# amc7135-by-16-19mm-led-aux-driver-mk-1_0.net
KiCad netlist of a schematic drawn in EAGLE
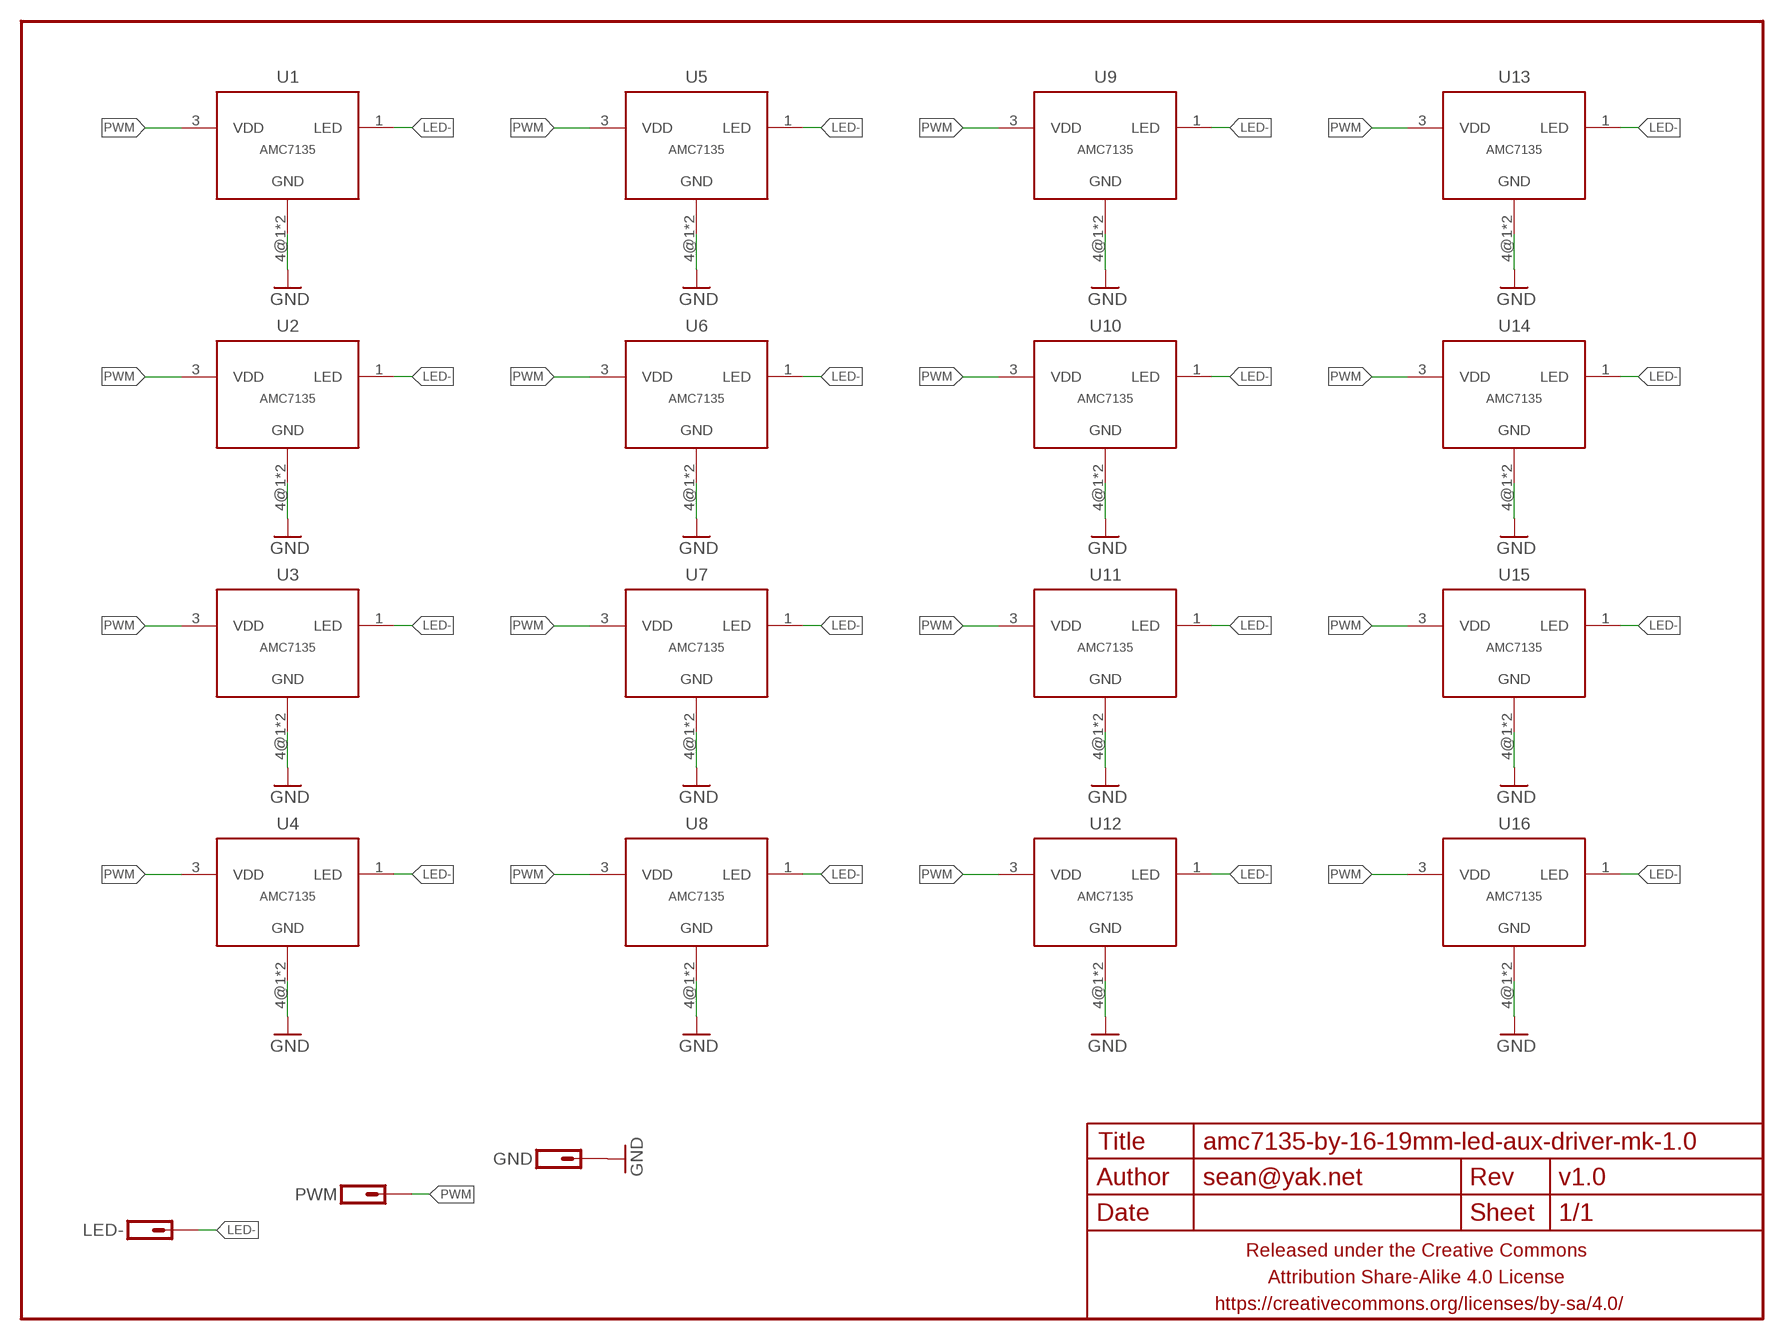
[diagram p0: schematic, sheet 1]

(export (version "E")
  (design (tool "Eeschema 10.0.6"))
  (components
    (comp (ref "FRAME1")
      (value "FRAME-LETTERNO_PACKAGE")
      (footprint "eagle-import:DUMMY")
      (fields (field (name "DESIGNER") "sean@yak.net") (field (name "VERSION") "v1.0"))
      (libsource (lib "eagle-import") (part "FRAME-LETTERNO_PACKAGE"))
    )
    (comp (ref "GND")
      (value "M01PTH-1.2MM-NS")
      (footprint "eagle-import:1X01-1.2MM-NS")
      (libsource (lib "eagle-import") (part "M01PTH-1.2MM-NS"))
    )
    (comp (ref "LED-")
      (value "M01PTH-1.2MM-NS")
      (footprint "eagle-import:1X01-1.2MM-NS")
      (libsource (lib "eagle-import") (part "M01PTH-1.2MM-NS"))
    )
    (comp (ref "PWM")
      (value "M01PTH-0.9MM-CIR")
      (footprint "eagle-import:1X01-0.9MM-CIR")
      (libsource (lib "eagle-import") (part "M01PTH-0.9MM-CIR"))
    )
    (comp (ref "U1")
      (value "AMC7135")
      (footprint "eagle-import:SOT89-ROUNDED-SMALLER")
      (libsource (lib "eagle-import") (part "AMC7135ROUNDEDSMALER"))
    )
    (comp (ref "U2")
      (value "AMC7135")
      (footprint "eagle-import:SOT89-ROUNDED-SMALLER")
      (libsource (lib "eagle-import") (part "AMC7135ROUNDEDSMALER"))
    )
    (comp (ref "U3")
      (value "AMC7135")
      (footprint "eagle-import:SOT89-ROUNDED-SMALLER")
      (libsource (lib "eagle-import") (part "AMC7135ROUNDEDSMALER"))
    )
    (comp (ref "U4")
      (value "AMC7135")
      (footprint "eagle-import:SOT89-ROUNDED-SMALLER")
      (libsource (lib "eagle-import") (part "AMC7135ROUNDEDSMALER"))
    )
    (comp (ref "U5")
      (value "AMC7135")
      (footprint "eagle-import:SOT89-ROUNDED-SMALLER")
      (libsource (lib "eagle-import") (part "AMC7135ROUNDEDSMALER"))
    )
    (comp (ref "U6")
      (value "AMC7135")
      (footprint "eagle-import:SOT89-ROUNDED-SMALLER")
      (libsource (lib "eagle-import") (part "AMC7135ROUNDEDSMALER"))
    )
    (comp (ref "U7")
      (value "AMC7135")
      (footprint "eagle-import:SOT89-ROUNDED-SMALLER")
      (libsource (lib "eagle-import") (part "AMC7135ROUNDEDSMALER"))
    )
    (comp (ref "U8")
      (value "AMC7135")
      (footprint "eagle-import:SOT89-ROUNDED-SMALLER")
      (libsource (lib "eagle-import") (part "AMC7135ROUNDEDSMALER"))
    )
    (comp (ref "U9")
      (value "AMC7135")
      (footprint "eagle-import:SOT89-ROUNDED-SMALLER")
      (libsource (lib "eagle-import") (part "AMC7135ROUNDEDSMALER"))
    )
    (comp (ref "U10")
      (value "AMC7135")
      (footprint "eagle-import:SOT89-ROUNDED-SMALLER")
      (libsource (lib "eagle-import") (part "AMC7135ROUNDEDSMALER"))
    )
    (comp (ref "U11")
      (value "AMC7135")
      (footprint "eagle-import:SOT89-ROUNDED-SMALLER")
      (libsource (lib "eagle-import") (part "AMC7135ROUNDEDSMALER"))
    )
    (comp (ref "U12")
      (value "AMC7135")
      (footprint "eagle-import:SOT89-ROUNDED-SMALLER")
      (libsource (lib "eagle-import") (part "AMC7135ROUNDEDSMALER"))
    )
    (comp (ref "U13")
      (value "AMC7135")
      (footprint "eagle-import:SOT89-ROUNDED-SMALLER")
      (libsource (lib "eagle-import") (part "AMC7135ROUNDEDSMALER"))
    )
    (comp (ref "U14")
      (value "AMC7135")
      (footprint "eagle-import:SOT89-ROUNDED-SMALLER")
      (libsource (lib "eagle-import") (part "AMC7135ROUNDEDSMALER"))
    )
    (comp (ref "U15")
      (value "AMC7135")
      (footprint "eagle-import:SOT89-ROUNDED-SMALLER")
      (libsource (lib "eagle-import") (part "AMC7135ROUNDEDSMALER"))
    )
    (comp (ref "U16")
      (value "AMC7135")
      (footprint "eagle-import:SOT89-ROUNDED-SMALLER")
      (libsource (lib "eagle-import") (part "AMC7135ROUNDEDSMALER"))
    )
  )
  (nets
    (net (code "1") (name "GND") (class "Default")
      (node (ref "GND") (pin "P$1") (pinfunction "1_P$1") (pintype "passive"))
      (node (ref "U1") (pin "4@1") (pinfunction "GND_4@1") (pintype "bidirectional"))
      (node (ref "U1") (pin "4@2") (pinfunction "GND_4@2") (pintype "bidirectional"))
      (node (ref "U10") (pin "4@1") (pinfunction "GND_4@1") (pintype "bidirectional"))
      (node (ref "U10") (pin "4@2") (pinfunction "GND_4@2") (pintype "bidirectional"))
      (node (ref "U11") (pin "4@1") (pinfunction "GND_4@1") (pintype "bidirectional"))
      (node (ref "U11") (pin "4@2") (pinfunction "GND_4@2") (pintype "bidirectional"))
      (node (ref "U12") (pin "4@1") (pinfunction "GND_4@1") (pintype "bidirectional"))
      (node (ref "U12") (pin "4@2") (pinfunction "GND_4@2") (pintype "bidirectional"))
      (node (ref "U13") (pin "4@1") (pinfunction "GND_4@1") (pintype "bidirectional"))
      (node (ref "U13") (pin "4@2") (pinfunction "GND_4@2") (pintype "bidirectional"))
      (node (ref "U14") (pin "4@1") (pinfunction "GND_4@1") (pintype "bidirectional"))
      (node (ref "U14") (pin "4@2") (pinfunction "GND_4@2") (pintype "bidirectional"))
      (node (ref "U15") (pin "4@1") (pinfunction "GND_4@1") (pintype "bidirectional"))
      (node (ref "U15") (pin "4@2") (pinfunction "GND_4@2") (pintype "bidirectional"))
      (node (ref "U16") (pin "4@1") (pinfunction "GND_4@1") (pintype "bidirectional"))
      (node (ref "U16") (pin "4@2") (pinfunction "GND_4@2") (pintype "bidirectional"))
      (node (ref "U2") (pin "4@1") (pinfunction "GND_4@1") (pintype "bidirectional"))
      (node (ref "U2") (pin "4@2") (pinfunction "GND_4@2") (pintype "bidirectional"))
      (node (ref "U3") (pin "4@1") (pinfunction "GND_4@1") (pintype "bidirectional"))
      (node (ref "U3") (pin "4@2") (pinfunction "GND_4@2") (pintype "bidirectional"))
      (node (ref "U4") (pin "4@1") (pinfunction "GND_4@1") (pintype "bidirectional"))
      (node (ref "U4") (pin "4@2") (pinfunction "GND_4@2") (pintype "bidirectional"))
      (node (ref "U5") (pin "4@1") (pinfunction "GND_4@1") (pintype "bidirectional"))
      (node (ref "U5") (pin "4@2") (pinfunction "GND_4@2") (pintype "bidirectional"))
      (node (ref "U6") (pin "4@1") (pinfunction "GND_4@1") (pintype "bidirectional"))
      (node (ref "U6") (pin "4@2") (pinfunction "GND_4@2") (pintype "bidirectional"))
      (node (ref "U7") (pin "4@1") (pinfunction "GND_4@1") (pintype "bidirectional"))
      (node (ref "U7") (pin "4@2") (pinfunction "GND_4@2") (pintype "bidirectional"))
      (node (ref "U8") (pin "4@1") (pinfunction "GND_4@1") (pintype "bidirectional"))
      (node (ref "U8") (pin "4@2") (pinfunction "GND_4@2") (pintype "bidirectional"))
      (node (ref "U9") (pin "4@1") (pinfunction "GND_4@1") (pintype "bidirectional"))
      (node (ref "U9") (pin "4@2") (pinfunction "GND_4@2") (pintype "bidirectional"))
    )
    (net (code "2") (name "LED-") (class "Default")
      (node (ref "LED-") (pin "P$1") (pinfunction "1_P$1") (pintype "passive"))
      (node (ref "U1") (pin "1") (pinfunction "LED_1") (pintype "bidirectional"))
      (node (ref "U10") (pin "1") (pinfunction "LED_1") (pintype "bidirectional"))
      (node (ref "U11") (pin "1") (pinfunction "LED_1") (pintype "bidirectional"))
      (node (ref "U12") (pin "1") (pinfunction "LED_1") (pintype "bidirectional"))
      (node (ref "U13") (pin "1") (pinfunction "LED_1") (pintype "bidirectional"))
      (node (ref "U14") (pin "1") (pinfunction "LED_1") (pintype "bidirectional"))
      (node (ref "U15") (pin "1") (pinfunction "LED_1") (pintype "bidirectional"))
      (node (ref "U16") (pin "1") (pinfunction "LED_1") (pintype "bidirectional"))
      (node (ref "U2") (pin "1") (pinfunction "LED_1") (pintype "bidirectional"))
      (node (ref "U3") (pin "1") (pinfunction "LED_1") (pintype "bidirectional"))
      (node (ref "U4") (pin "1") (pinfunction "LED_1") (pintype "bidirectional"))
      (node (ref "U5") (pin "1") (pinfunction "LED_1") (pintype "bidirectional"))
      (node (ref "U6") (pin "1") (pinfunction "LED_1") (pintype "bidirectional"))
      (node (ref "U7") (pin "1") (pinfunction "LED_1") (pintype "bidirectional"))
      (node (ref "U8") (pin "1") (pinfunction "LED_1") (pintype "bidirectional"))
      (node (ref "U9") (pin "1") (pinfunction "LED_1") (pintype "bidirectional"))
    )
    (net (code "3") (name "PWM") (class "Default")
      (node (ref "PWM") (pin "P$1") (pinfunction "1_P$1") (pintype "passive"))
      (node (ref "U1") (pin "3") (pinfunction "VDD_3") (pintype "bidirectional"))
      (node (ref "U10") (pin "3") (pinfunction "VDD_3") (pintype "bidirectional"))
      (node (ref "U11") (pin "3") (pinfunction "VDD_3") (pintype "bidirectional"))
      (node (ref "U12") (pin "3") (pinfunction "VDD_3") (pintype "bidirectional"))
      (node (ref "U13") (pin "3") (pinfunction "VDD_3") (pintype "bidirectional"))
      (node (ref "U14") (pin "3") (pinfunction "VDD_3") (pintype "bidirectional"))
      (node (ref "U15") (pin "3") (pinfunction "VDD_3") (pintype "bidirectional"))
      (node (ref "U16") (pin "3") (pinfunction "VDD_3") (pintype "bidirectional"))
      (node (ref "U2") (pin "3") (pinfunction "VDD_3") (pintype "bidirectional"))
      (node (ref "U3") (pin "3") (pinfunction "VDD_3") (pintype "bidirectional"))
      (node (ref "U4") (pin "3") (pinfunction "VDD_3") (pintype "bidirectional"))
      (node (ref "U5") (pin "3") (pinfunction "VDD_3") (pintype "bidirectional"))
      (node (ref "U6") (pin "3") (pinfunction "VDD_3") (pintype "bidirectional"))
      (node (ref "U7") (pin "3") (pinfunction "VDD_3") (pintype "bidirectional"))
      (node (ref "U8") (pin "3") (pinfunction "VDD_3") (pintype "bidirectional"))
      (node (ref "U9") (pin "3") (pinfunction "VDD_3") (pintype "bidirectional"))
    )
  )
)
